# digAudio-rcj-da101jc.net
KiCad netlist of a schematic drawn in EAGLE
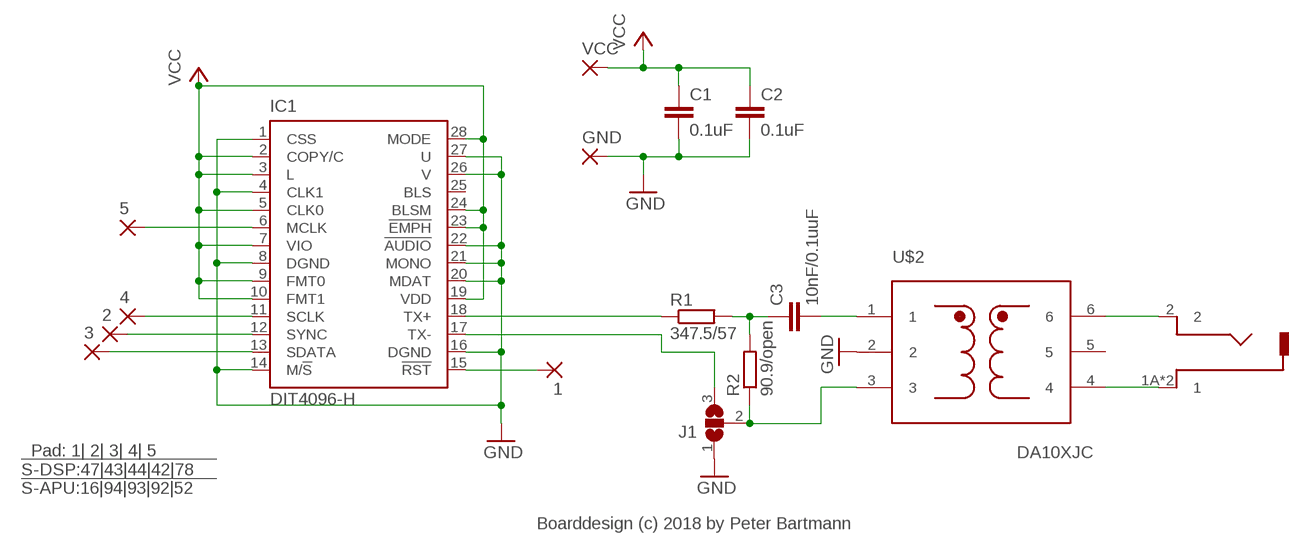
[diagram p0: schematic, sheet 1]

(export (version "E")
  (design (tool "Eeschema 10.0.6"))
  (components
    (comp (ref "1")
      (value "SMD1")
      (footprint "eagle-import:SMD0,8-1,6")
      (libsource (lib "eagle-import") (part "SMD1"))
    )
    (comp (ref "2")
      (value "SMD1")
      (footprint "eagle-import:SMD0,8-1,6")
      (libsource (lib "eagle-import") (part "SMD1"))
    )
    (comp (ref "3")
      (value "SMD1")
      (footprint "eagle-import:SMD0,8-1,6")
      (libsource (lib "eagle-import") (part "SMD1"))
    )
    (comp (ref "4")
      (value "SMD1")
      (footprint "eagle-import:SMD0,8-1,6")
      (libsource (lib "eagle-import") (part "SMD1"))
    )
    (comp (ref "5")
      (value "SMD1")
      (footprint "eagle-import:SMD0,8-1,6")
      (libsource (lib "eagle-import") (part "SMD1"))
    )
    (comp (ref "C1")
      (value "0.1uF")
      (footprint "eagle-import:C0603")
      (libsource (lib "eagle-import") (part "C-EUC0603"))
    )
    (comp (ref "C2")
      (value "0.1uF")
      (footprint "eagle-import:C0603")
      (libsource (lib "eagle-import") (part "C-EUC0603"))
    )
    (comp (ref "C3")
      (value "10nF/0.1uuF")
      (footprint "eagle-import:C0603")
      (libsource (lib "eagle-import") (part "C-EUC0603"))
    )
    (comp (ref "GND")
      (value "1,6/0,9")
      (footprint "eagle-import:1,6_0,9")
      (libsource (lib "eagle-import") (part "1,6/0,9"))
    )
    (comp (ref "IC1")
      (value "DIT4096-H")
      (footprint "eagle-import:PW_R-PDSO-G28")
      (fields (field (name "MF") "TEXAS INSTRUMENTS") (field (name "MPN") "DIT4192IPW"))
      (libsource (lib "eagle-import") (part "DIT4192-H"))
    )
    (comp (ref "J1")
      (value "SJ2W")
      (footprint "eagle-import:SJ_2")
      (libsource (lib "eagle-import") (part "SJ2W"))
    )
    (comp (ref "R1")
      (value "347.5/57")
      (footprint "eagle-import:R0603")
      (libsource (lib "eagle-import") (part "R-EU_R0603"))
    )
    (comp (ref "R2")
      (value "90.9/open")
      (footprint "eagle-import:R0603")
      (libsource (lib "eagle-import") (part "R-EU_R0603"))
    )
    (comp (ref "U$1")
      (value "RCJ-013-SMT-TR")
      (footprint "eagle-import:RCJ_01X_SMT_MODIFIED")
      (libsource (lib "eagle-import") (part "RCJ_01X_SMT-MODIFIED"))
    )
    (comp (ref "U$2")
      (value "DA10XJC")
      (footprint "eagle-import:DA101JC")
      (libsource (lib "eagle-import") (part "DA10XJC"))
    )
    (comp (ref "VCC")
      (value "1,6/0,9")
      (footprint "eagle-import:1,6_0,9")
      (libsource (lib "eagle-import") (part "1,6/0,9"))
    )
  )
  (nets
    (net (code "1") (name "GND") (class "Default")
      (node (ref "C1") (pin "2") (pinfunction "2_2") (pintype "passive"))
      (node (ref "C2") (pin "2") (pinfunction "2_2") (pintype "passive"))
      (node (ref "GND") (pin "1") (pinfunction "P_1") (pintype "passive"))
      (node (ref "IC1") (pin "1") (pinfunction "CSS_1") (pintype "input"))
      (node (ref "IC1") (pin "14") (pinfunction "M/~{S}_14") (pintype "input"))
      (node (ref "IC1") (pin "16") (pinfunction "DGND_16") (pintype "power_in"))
      (node (ref "IC1") (pin "20") (pinfunction "MDAT_20") (pintype "input"))
      (node (ref "IC1") (pin "21") (pinfunction "MONO_21") (pintype "input"))
      (node (ref "IC1") (pin "22") (pinfunction "~{AUDIO}_22") (pintype "input"))
      (node (ref "IC1") (pin "26") (pinfunction "V_26") (pintype "input"))
      (node (ref "IC1") (pin "27") (pinfunction "U_27") (pintype "input"))
      (node (ref "IC1") (pin "4") (pinfunction "CLK1_4") (pintype "input"))
      (node (ref "IC1") (pin "8") (pinfunction "DGND_8") (pintype "power_in"))
      (node (ref "J1") (pin "1") (pinfunction "1_1") (pintype "passive"))
      (node (ref "U$2") (pin "2") (pinfunction "2_2") (pintype "bidirectional"))
    )
    (net (code "2") (name "Net-(1-P)") (class "Default")
      (node (ref "1") (pin "P$1") (pinfunction "P_P$1") (pintype "passive"))
      (node (ref "IC1") (pin "15") (pinfunction "~{RST}_15") (pintype "input"))
    )
    (net (code "3") (name "Net-(2-P)") (class "Default")
      (node (ref "2") (pin "P$1") (pinfunction "P_P$1") (pintype "passive"))
      (node (ref "IC1") (pin "12") (pinfunction "SYNC_12") (pintype "bidirectional"))
    )
    (net (code "4") (name "Net-(3-P)") (class "Default")
      (node (ref "3") (pin "P$1") (pinfunction "P_P$1") (pintype "passive"))
      (node (ref "IC1") (pin "13") (pinfunction "SDATA_13") (pintype "input"))
    )
    (net (code "5") (name "Net-(4-P)") (class "Default")
      (node (ref "4") (pin "P$1") (pinfunction "P_P$1") (pintype "passive"))
      (node (ref "IC1") (pin "11") (pinfunction "SCLK_11") (pintype "bidirectional"))
    )
    (net (code "6") (name "Net-(5-P)") (class "Default")
      (node (ref "5") (pin "P$1") (pinfunction "P_P$1") (pintype "passive"))
      (node (ref "IC1") (pin "6") (pinfunction "MCLK_6") (pintype "input"))
    )
    (net (code "7") (name "Net-(C3-Pad1)") (class "Default")
      (node (ref "C3") (pin "1") (pinfunction "1_1") (pintype "passive"))
      (node (ref "R1") (pin "2") (pinfunction "2_2") (pintype "passive"))
      (node (ref "R2") (pin "2") (pinfunction "2_2") (pintype "passive"))
    )
    (net (code "8") (name "Net-(C3-Pad2)") (class "Default")
      (node (ref "C3") (pin "2") (pinfunction "2_2") (pintype "passive"))
      (node (ref "U$2") (pin "1") (pinfunction "1_1") (pintype "bidirectional"))
    )
    (net (code "9") (name "Net-(IC1-TX+)") (class "Default")
      (node (ref "IC1") (pin "18") (pinfunction "TX+_18") (pintype "output"))
      (node (ref "R1") (pin "1") (pinfunction "1_1") (pintype "passive"))
    )
    (net (code "10") (name "Net-(IC1-TX-)") (class "Default")
      (node (ref "IC1") (pin "17") (pinfunction "TX-_17") (pintype "output"))
      (node (ref "J1") (pin "3") (pinfunction "3_3") (pintype "passive"))
    )
    (net (code "11") (name "Net-(J1-Pad2)") (class "Default")
      (node (ref "J1") (pin "2") (pinfunction "2_2") (pintype "passive"))
      (node (ref "R2") (pin "1") (pinfunction "1_1") (pintype "passive"))
      (node (ref "U$2") (pin "3") (pinfunction "3_3") (pintype "bidirectional"))
    )
    (net (code "12") (name "Net-(U$1-1-Pad1A)") (class "Default")
      (node (ref "U$1") (pin "1A") (pinfunction "1_1A") (pintype "bidirectional"))
      (node (ref "U$1") (pin "1B") (pinfunction "1_1B") (pintype "bidirectional"))
      (node (ref "U$2") (pin "4") (pinfunction "4_4") (pintype "bidirectional"))
    )
    (net (code "13") (name "Net-(U$1-Pad2)") (class "Default")
      (node (ref "U$1") (pin "2") (pinfunction "2_2") (pintype "bidirectional"))
      (node (ref "U$2") (pin "6") (pinfunction "6_6") (pintype "bidirectional"))
    )
    (net (code "14") (name "VCC") (class "Default")
      (node (ref "C1") (pin "1") (pinfunction "1_1") (pintype "passive"))
      (node (ref "C2") (pin "1") (pinfunction "1_1") (pintype "passive"))
      (node (ref "IC1") (pin "10") (pinfunction "FMT1_10") (pintype "input"))
      (node (ref "IC1") (pin "19") (pinfunction "VDD_19") (pintype "power_in"))
      (node (ref "IC1") (pin "2") (pinfunction "COPY/C_2") (pintype "input"))
      (node (ref "IC1") (pin "23") (pinfunction "~{EMPH}_23") (pintype "input"))
      (node (ref "IC1") (pin "24") (pinfunction "BLSM_24") (pintype "input"))
      (node (ref "IC1") (pin "28") (pinfunction "MODE_28") (pintype "input"))
      (node (ref "IC1") (pin "3") (pinfunction "L_3") (pintype "input"))
      (node (ref "IC1") (pin "5") (pinfunction "CLK0_5") (pintype "input"))
      (node (ref "IC1") (pin "7") (pinfunction "VIO_7") (pintype "power_in"))
      (node (ref "IC1") (pin "9") (pinfunction "FMT0_9") (pintype "input"))
      (node (ref "VCC") (pin "1") (pinfunction "P_1") (pintype "passive"))
    )
    (net (code "15") (name "unconnected-(IC1-BLS-Pad25)") (class "Default")
      (node (ref "IC1") (pin "25") (pinfunction "BLS_25") (pintype "bidirectional"))
    )
    (net (code "16") (name "unconnected-(U$2-Pad5)") (class "Default")
      (node (ref "U$2") (pin "5") (pinfunction "5_5") (pintype "bidirectional"))
    )
  )
)
